# Sheet2.net
KiCad netlist of a schematic drawn in Altium Designer
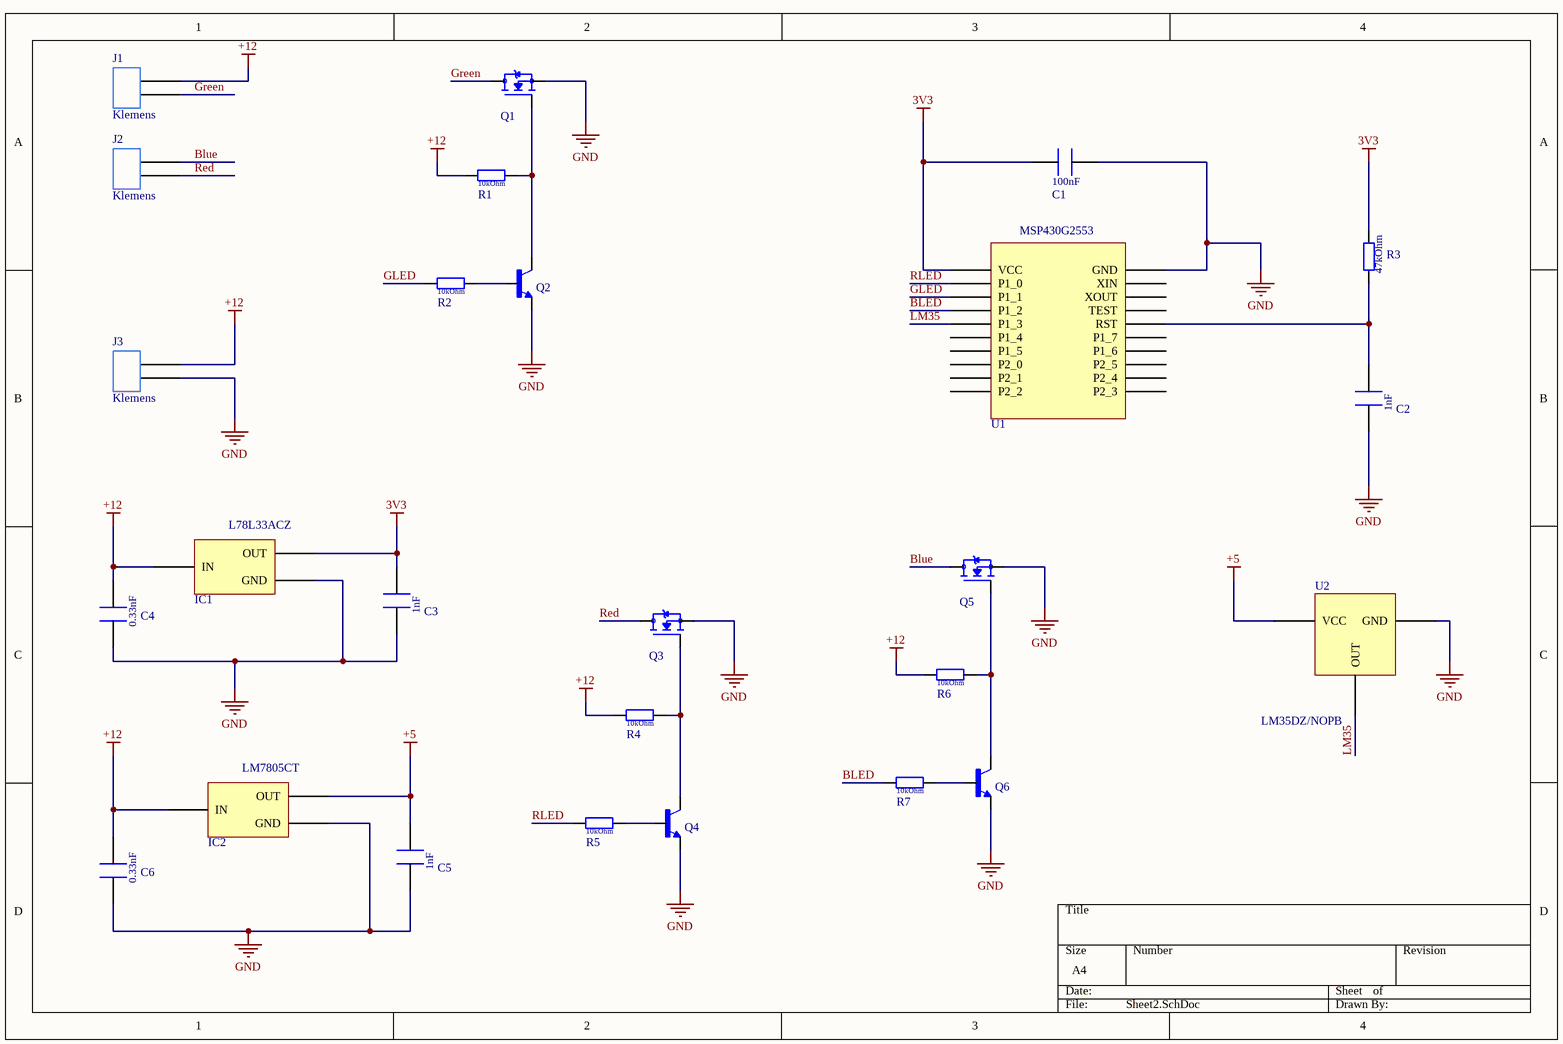
[diagram p0: Sheet2.SchDoc]

(export (version "E")
  (design (tool "Eeschema 10.0.6"))
  (components
    (comp (ref "C1")
      (value "100nF Cap")
      (footprint "Capacitor")
      (libsource (lib "MSP_LM35") (part "100nF Cap"))
    )
    (comp (ref "C2") (value "1nF Cap") (footprint "Capacitor") (libsource (lib "MSP_LM35") (part "1nF Cap")))
    (comp (ref "C3")
      (value "0.1uF Cap")
      (footprint "Capacitor")
      (libsource (lib "MSP_LM35") (part "0.1uF Cap"))
    )
    (comp (ref "C4")
      (value "0.33uF Cap")
      (footprint "Capacitor")
      (libsource (lib "MSP_LM35") (part "0.33uF Cap"))
    )
    (comp (ref "C5")
      (value "0.1uF Cap")
      (footprint "Capacitor")
      (libsource (lib "MSP_LM35") (part "0.1uF Cap"))
    )
    (comp (ref "C6")
      (value "0.33uF Cap")
      (footprint "Capacitor")
      (libsource (lib "MSP_LM35") (part "0.33uF Cap"))
    )
    (comp (ref "IC1")
      (value "L78L Series 100 mA 3.3 V Positive Voltage Regulator Through Hole - TO-92")
      (footprint "L78L33")
      (fields
        (field (name "MANUFACTURER") "STMicroelectronics")
        (field (name "MANUFACTURER PART NUMBER") "L78L33ACZ")
      )
      (libsource (lib "MSP_LM35") (part "L78L33"))
    )
    (comp (ref "IC2")
      (value "LM78XX Series 5 V Fixed Output 1 A 3-Terminal LDO Voltage Regulator - TO-220")
      (footprint "LM7805")
      (fields
        (field (name "MANUFACTURER") "ON Semiconductor / Fairchild")
        (field (name "MANUFACTURER PART NUMBER") "LM7805CT")
      )
      (libsource (lib "MSP_LM35") (part "LM7805"))
    )
    (comp (ref "J1") (value "Klemens") (footprint "Klemens") (libsource (lib "MSP_LM35") (part "Klemens")))
    (comp (ref "J2") (value "Klemens") (footprint "Klemens") (libsource (lib "MSP_LM35") (part "Klemens")))
    (comp (ref "J3") (value "Klemens") (footprint "Klemens") (libsource (lib "MSP_LM35") (part "Klemens")))
    (comp (ref "Q1")
      (value "MOSFET, Power; N-Ch; VDSS 55V; RDS(ON) 17.5 Milliohms; ID 49A; TO-220AB; PD 94W; -55deg")
      (footprint "IRFZ44N")
      (fields
        (field (name "MANUFACTURER") "International Rectifier")
        (field (name "MANUFACTURER PART NUMBER") "IRFZ44N")
      )
      (libsource (lib "MSP_LM35") (part "IRFZ44N"))
    )
    (comp (ref "Q2")
      (value "Trans GP BJT NPN 45V 0.1A 500mW Automotive 3-Pin TO-92 Ammo")
      (footprint "BC547")
      (fields
        (field (name "MANUFACTURER") "ON Semiconductor / Fairchild")
        (field (name "MANUFACTURER PART NUMBER") "BC547B")
        (field (name "VOLTAGE") "40V")
      )
      (libsource (lib "MSP_LM35") (part "BC547B"))
    )
    (comp (ref "Q3")
      (value "MOSFET, Power; N-Ch; VDSS 55V; RDS(ON) 17.5 Milliohms; ID 49A; TO-220AB; PD 94W; -55deg")
      (footprint "IRFZ44N")
      (fields
        (field (name "MANUFACTURER") "International Rectifier")
        (field (name "MANUFACTURER PART NUMBER") "IRFZ44N")
      )
      (libsource (lib "MSP_LM35") (part "IRFZ44N"))
    )
    (comp (ref "Q4")
      (value "Trans GP BJT NPN 45V 0.1A 500mW Automotive 3-Pin TO-92 Ammo")
      (footprint "BC547")
      (fields
        (field (name "MANUFACTURER") "ON Semiconductor / Fairchild")
        (field (name "MANUFACTURER PART NUMBER") "BC547B")
        (field (name "VOLTAGE") "40V")
      )
      (libsource (lib "MSP_LM35") (part "BC547B"))
    )
    (comp (ref "Q5")
      (value "MOSFET, Power; N-Ch; VDSS 55V; RDS(ON) 17.5 Milliohms; ID 49A; TO-220AB; PD 94W; -55deg")
      (footprint "IRFZ44N")
      (fields
        (field (name "MANUFACTURER") "International Rectifier")
        (field (name "MANUFACTURER PART NUMBER") "IRFZ44N")
      )
      (libsource (lib "MSP_LM35") (part "IRFZ44N"))
    )
    (comp (ref "Q6")
      (value "Trans GP BJT NPN 45V 0.1A 500mW Automotive 3-Pin TO-92 Ammo")
      (footprint "BC547")
      (fields
        (field (name "MANUFACTURER") "ON Semiconductor / Fairchild")
        (field (name "MANUFACTURER PART NUMBER") "BC547B")
        (field (name "VOLTAGE") "40V")
      )
      (libsource (lib "MSP_LM35") (part "BC547B"))
    )
    (comp (ref "R1") (value "10kOhm Res") (footprint "Res") (libsource (lib "MSP_LM35") (part "10kOhm Res")))
    (comp (ref "R2") (value "10kOhm Res") (footprint "Res") (libsource (lib "MSP_LM35") (part "10kOhm Res")))
    (comp (ref "R3") (value "47kOhm Res") (footprint "Res") (libsource (lib "MSP_LM35") (part "47kOhm Res")))
    (comp (ref "R4") (value "10kOhm Res") (footprint "Res") (libsource (lib "MSP_LM35") (part "10kOhm Res")))
    (comp (ref "R5") (value "10kOhm Res") (footprint "Res") (libsource (lib "MSP_LM35") (part "10kOhm Res")))
    (comp (ref "R6") (value "10kOhm Res") (footprint "Res") (libsource (lib "MSP_LM35") (part "10kOhm Res")))
    (comp (ref "R7") (value "10kOhm Res") (footprint "Res") (libsource (lib "MSP_LM35") (part "10kOhm Res")))
    (comp (ref "U1")
      (value "16 MHz MCU with 16KB Flash, 512B SRAM, comparator, UART/SPI/I2C, timer 20-PDIP -40 to 85")
      (footprint "MSP430G2553")
      (fields
        (field (name "MANUFACTURER") "Texas Instruments")
        (field (name "MANUFACTURER PART NUMBER") "MSP430G2553IN20")
      )
      (libsource (lib "MSP_LM35") (part "MSP430G2553"))
    )
    (comp (ref "U2")
      (value "Temperature Sensor Analog, Local 0°C ~ 100°C 10mV/°C TO-92-3")
      (footprint "LM35")
      (fields
        (field (name "MANUFACTURER") "TI National Semiconductor")
        (field (name "MANUFACTURER PART NUMBER") "LM35DZ/NOPB")
      )
      (libsource (lib "MSP_LM35") (part "LM35"))
    )
  )
  (nets
    (net (code "1") (name "+5") (class "Default")
      (node (ref "C5") (pin "1") (pinfunction "1_1") (pintype "passive"))
      (node (ref "IC2") (pin "3") (pinfunction "OUT_3") (pintype "passive"))
      (node (ref "U2") (pin "1") (pinfunction "VCC_1") (pintype "passive"))
    )
    (net (code "2") (name "+12") (class "Default")
      (node (ref "C4") (pin "1") (pinfunction "1_1") (pintype "passive"))
      (node (ref "C6") (pin "1") (pinfunction "1_1") (pintype "passive"))
      (node (ref "IC1") (pin "3") (pinfunction "IN_3") (pintype "passive"))
      (node (ref "IC2") (pin "1") (pinfunction "IN_1") (pintype "passive"))
      (node (ref "J1") (pin "2") (pinfunction "2_2") (pintype "passive"))
      (node (ref "J3") (pin "2") (pinfunction "2_2") (pintype "passive"))
      (node (ref "R1") (pin "1") (pinfunction "1_1") (pintype "passive"))
      (node (ref "R4") (pin "1") (pinfunction "1_1") (pintype "passive"))
      (node (ref "R6") (pin "1") (pinfunction "1_1") (pintype "passive"))
    )
    (net (code "3") (name "/BLED") (class "Default")
      (node (ref "R7") (pin "1") (pinfunction "1_1") (pintype "passive"))
      (node (ref "U1") (pin "3") (pinfunction "P1_2_3") (pintype "passive"))
    )
    (net (code "4") (name "/Blue") (class "Default")
      (node (ref "J2") (pin "2") (pinfunction "2_2") (pintype "passive"))
      (node (ref "Q5") (pin "2") (pinfunction "D_2") (pintype "passive"))
    )
    (net (code "5") (name "/GLED") (class "Default")
      (node (ref "R2") (pin "1") (pinfunction "1_1") (pintype "passive"))
      (node (ref "U1") (pin "2") (pinfunction "P1_1_2") (pintype "passive"))
    )
    (net (code "6") (name "/Green") (class "Default")
      (node (ref "J1") (pin "1") (pinfunction "1_1") (pintype "passive"))
      (node (ref "Q1") (pin "2") (pinfunction "D_2") (pintype "passive"))
    )
    (net (code "7") (name "/LM35") (class "Default")
      (node (ref "U1") (pin "4") (pinfunction "P1_3_4") (pintype "passive"))
      (node (ref "U2") (pin "2") (pinfunction "OUT_2") (pintype "passive"))
    )
    (net (code "8") (name "/RLED") (class "Default")
      (node (ref "R5") (pin "1") (pinfunction "1_1") (pintype "passive"))
      (node (ref "U1") (pin "1") (pinfunction "P1_0_1") (pintype "passive"))
    )
    (net (code "9") (name "/Red") (class "Default")
      (node (ref "J2") (pin "1") (pinfunction "1_1") (pintype "passive"))
      (node (ref "Q3") (pin "2") (pinfunction "D_2") (pintype "passive"))
    )
    (net (code "10") (name "3V3") (class "Default")
      (node (ref "C1") (pin "0") (pinfunction "0_0") (pintype "passive"))
      (node (ref "C3") (pin "1") (pinfunction "1_1") (pintype "passive"))
      (node (ref "IC1") (pin "1") (pinfunction "OUT_1") (pintype "passive"))
      (node (ref "R3") (pin "2") (pinfunction "2_2") (pintype "passive"))
      (node (ref "U1") (pin "0") (pinfunction "VCC_0") (pintype "passive"))
    )
    (net (code "11") (name "GND") (class "Default")
      (node (ref "C1") (pin "1") (pinfunction "1_1") (pintype "passive"))
      (node (ref "C2") (pin "0") (pinfunction "0_0") (pintype "passive"))
      (node (ref "C3") (pin "0") (pinfunction "0_0") (pintype "passive"))
      (node (ref "C4") (pin "0") (pinfunction "0_0") (pintype "passive"))
      (node (ref "C5") (pin "0") (pinfunction "0_0") (pintype "passive"))
      (node (ref "C6") (pin "0") (pinfunction "0_0") (pintype "passive"))
      (node (ref "IC1") (pin "2") (pinfunction "GND_2") (pintype "passive"))
      (node (ref "IC2") (pin "2") (pinfunction "GND_2") (pintype "passive"))
      (node (ref "J3") (pin "1") (pinfunction "1_1") (pintype "passive"))
      (node (ref "Q1") (pin "3") (pinfunction "S_3") (pintype "passive"))
      (node (ref "Q2") (pin "3") (pinfunction "E_3") (pintype "passive"))
      (node (ref "Q3") (pin "3") (pinfunction "S_3") (pintype "passive"))
      (node (ref "Q4") (pin "3") (pinfunction "E_3") (pintype "passive"))
      (node (ref "Q5") (pin "3") (pinfunction "S_3") (pintype "passive"))
      (node (ref "Q6") (pin "3") (pinfunction "E_3") (pintype "passive"))
      (node (ref "U1") (pin "19") (pinfunction "GND_19") (pintype "passive"))
      (node (ref "U2") (pin "3") (pinfunction "GND_3") (pintype "passive"))
    )
    (net (code "12") (name "Net-(Q1-G)") (class "Default")
      (node (ref "Q1") (pin "1") (pinfunction "G_1") (pintype "passive"))
      (node (ref "Q2") (pin "1") (pinfunction "C_1") (pintype "passive"))
      (node (ref "R1") (pin "2") (pinfunction "2_2") (pintype "passive"))
    )
    (net (code "13") (name "Net-(Q2-B)") (class "Default")
      (node (ref "Q2") (pin "2") (pinfunction "B_2") (pintype "passive"))
      (node (ref "R2") (pin "2") (pinfunction "2_2") (pintype "passive"))
    )
    (net (code "14") (name "Net-(Q3-G)") (class "Default")
      (node (ref "Q3") (pin "1") (pinfunction "G_1") (pintype "passive"))
      (node (ref "Q4") (pin "1") (pinfunction "C_1") (pintype "passive"))
      (node (ref "R4") (pin "2") (pinfunction "2_2") (pintype "passive"))
    )
    (net (code "15") (name "Net-(Q4-B)") (class "Default")
      (node (ref "Q4") (pin "2") (pinfunction "B_2") (pintype "passive"))
      (node (ref "R5") (pin "2") (pinfunction "2_2") (pintype "passive"))
    )
    (net (code "16") (name "Net-(Q5-G)") (class "Default")
      (node (ref "Q5") (pin "1") (pinfunction "G_1") (pintype "passive"))
      (node (ref "Q6") (pin "1") (pinfunction "C_1") (pintype "passive"))
      (node (ref "R6") (pin "2") (pinfunction "2_2") (pintype "passive"))
    )
    (net (code "17") (name "Net-(Q6-B)") (class "Default")
      (node (ref "Q6") (pin "2") (pinfunction "B_2") (pintype "passive"))
      (node (ref "R7") (pin "2") (pinfunction "2_2") (pintype "passive"))
    )
    (net (code "18") (name "Net-(U1-RST)") (class "Default")
      (node (ref "C2") (pin "1") (pinfunction "1_1") (pintype "passive"))
      (node (ref "R3") (pin "1") (pinfunction "1_1") (pintype "passive"))
      (node (ref "U1") (pin "15") (pinfunction "RST_15") (pintype "passive"))
    )
    (net (code "19") (name "unconnected-(U1-P1_4-Pad5)") (class "Default")
      (node (ref "U1") (pin "5") (pinfunction "P1_4_5") (pintype "passive"))
    )
    (net (code "20") (name "unconnected-(U1-P1_5-Pad6)") (class "Default")
      (node (ref "U1") (pin "6") (pinfunction "P1_5_6") (pintype "passive"))
    )
    (net (code "21") (name "unconnected-(U1-P1_6-Pad13)") (class "Default")
      (node (ref "U1") (pin "13") (pinfunction "P1_6_13") (pintype "passive"))
    )
    (net (code "22") (name "unconnected-(U1-P1_7-Pad14)") (class "Default")
      (node (ref "U1") (pin "14") (pinfunction "P1_7_14") (pintype "passive"))
    )
    (net (code "23") (name "unconnected-(U1-P2_0-Pad7)") (class "Default")
      (node (ref "U1") (pin "7") (pinfunction "P2_0_7") (pintype "passive"))
    )
    (net (code "24") (name "unconnected-(U1-P2_1-Pad8)") (class "Default")
      (node (ref "U1") (pin "8") (pinfunction "P2_1_8") (pintype "passive"))
    )
    (net (code "25") (name "unconnected-(U1-P2_2-Pad9)") (class "Default")
      (node (ref "U1") (pin "9") (pinfunction "P2_2_9") (pintype "passive"))
    )
    (net (code "26") (name "unconnected-(U1-P2_3-Pad10)") (class "Default")
      (node (ref "U1") (pin "10") (pinfunction "P2_3_10") (pintype "passive"))
    )
    (net (code "27") (name "unconnected-(U1-P2_4-Pad11)") (class "Default")
      (node (ref "U1") (pin "11") (pinfunction "P2_4_11") (pintype "passive"))
    )
    (net (code "28") (name "unconnected-(U1-P2_5-Pad12)") (class "Default")
      (node (ref "U1") (pin "12") (pinfunction "P2_5_12") (pintype "passive"))
    )
    (net (code "29") (name "unconnected-(U1-TEST-Pad16)") (class "Default")
      (node (ref "U1") (pin "16") (pinfunction "TEST_16") (pintype "passive"))
    )
    (net (code "30") (name "unconnected-(U1-XIN-Pad18)") (class "Default")
      (node (ref "U1") (pin "18") (pinfunction "XIN_18") (pintype "passive"))
    )
    (net (code "31") (name "unconnected-(U1-XOUT-Pad17)") (class "Default")
      (node (ref "U1") (pin "17") (pinfunction "XOUT_17") (pintype "passive"))
    )
  )
)
